# Shift_Register_Module_v0_6.net
KiCad netlist of a schematic drawn in EAGLE
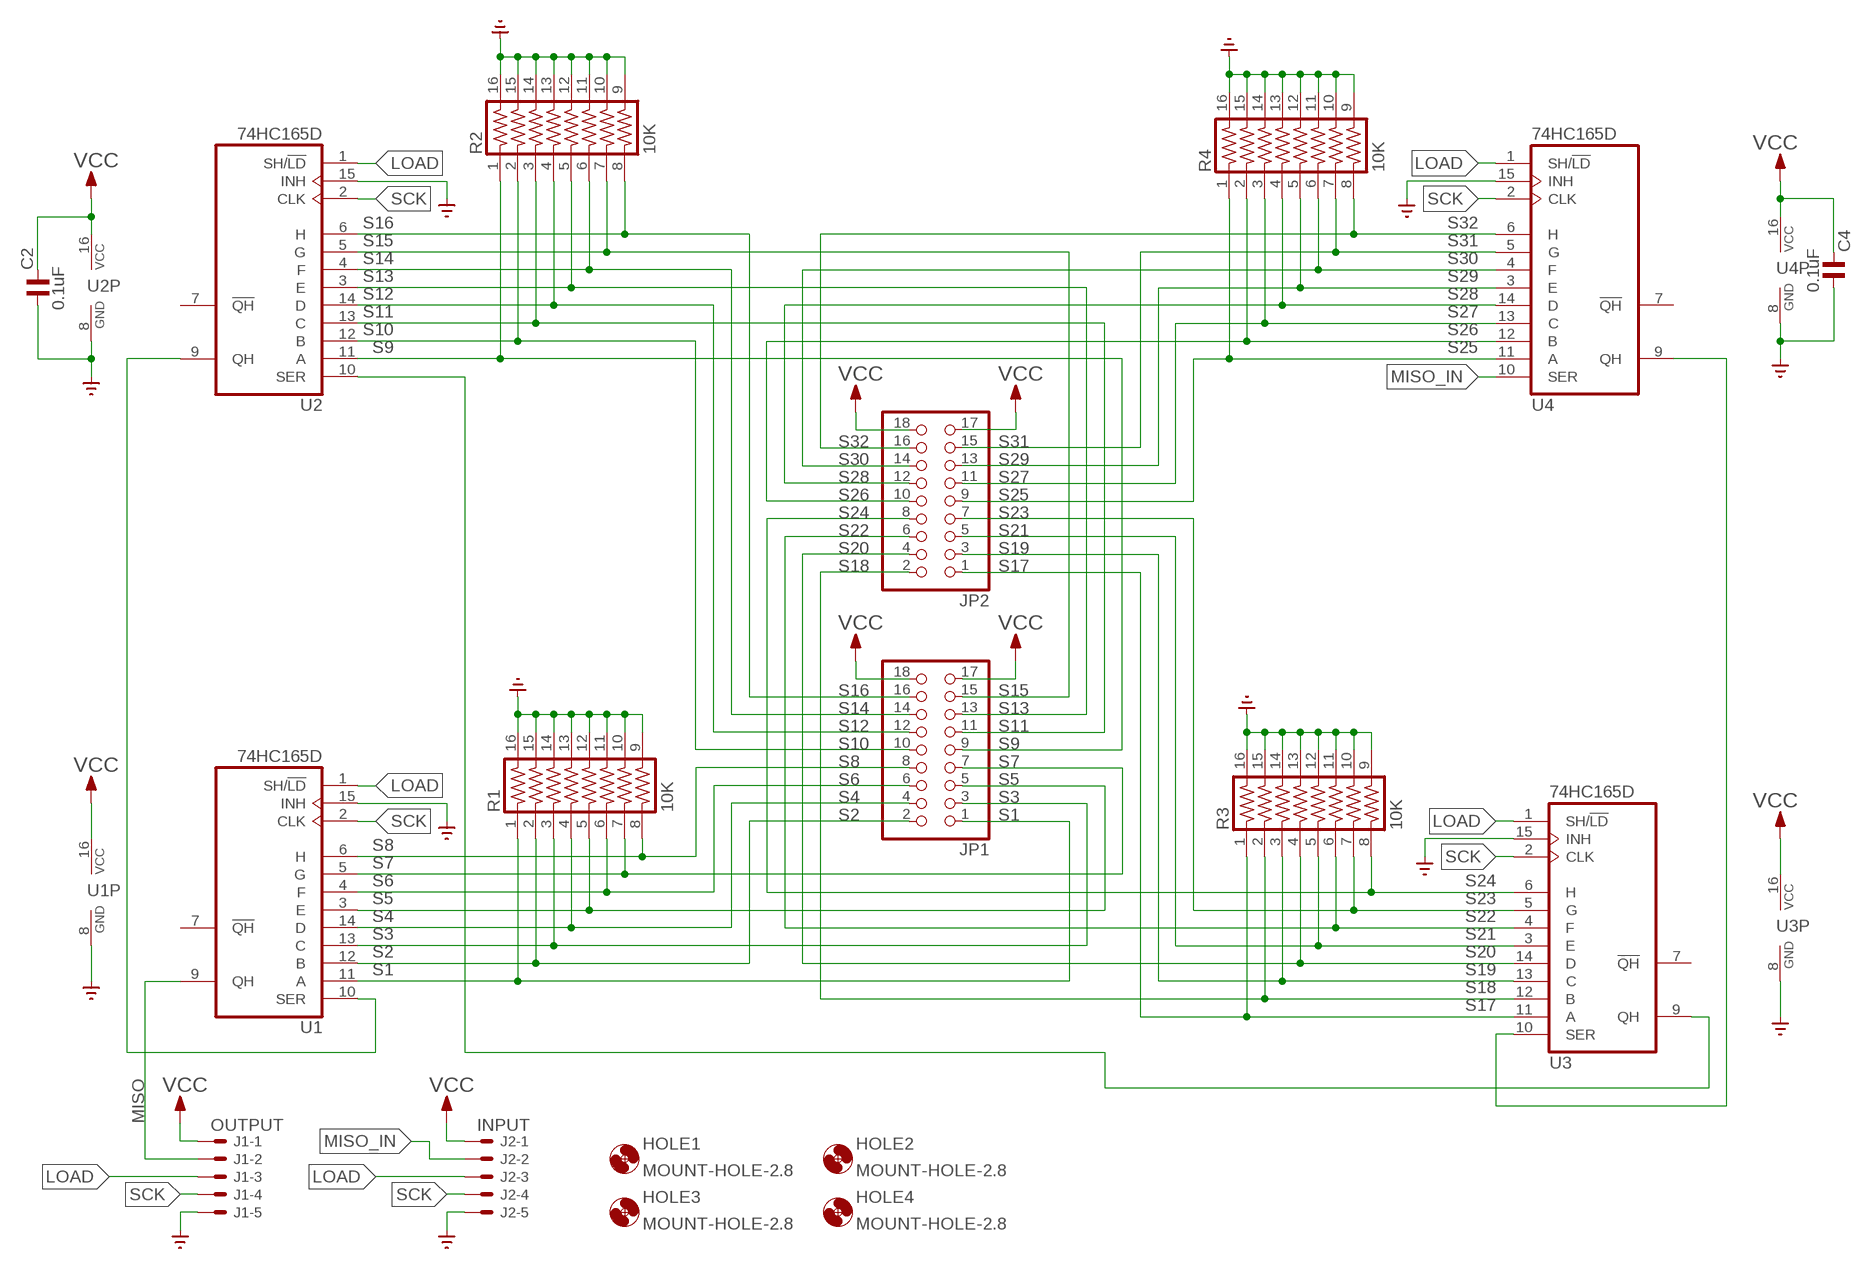
[diagram p0: schematic, sheet 1]

(export (version "E")
  (design (tool "Eeschema 10.0.6"))
  (components
    (comp (ref "C2")
      (value "0.1uF")
      (footprint "eagle-import:C0805MP")
      (libsource (lib "eagle-import") (part "C_0805MP"))
    )
    (comp (ref "C4")
      (value "0.1uF")
      (footprint "eagle-import:C0805MP")
      (libsource (lib "eagle-import") (part "C_0805MP"))
    )
    (comp (ref "HOLE1")
      (value "MOUNT-HOLE-2.8")
      (footprint "eagle-import:2,8")
      (libsource (lib "eagle-import") (part "MOUNT-HOLE-2.8"))
    )
    (comp (ref "HOLE2")
      (value "MOUNT-HOLE-2.8")
      (footprint "eagle-import:2,8")
      (libsource (lib "eagle-import") (part "MOUNT-HOLE-2.8"))
    )
    (comp (ref "HOLE3")
      (value "MOUNT-HOLE-2.8")
      (footprint "eagle-import:2,8")
      (libsource (lib "eagle-import") (part "MOUNT-HOLE-2.8"))
    )
    (comp (ref "HOLE4")
      (value "MOUNT-HOLE-2.8")
      (footprint "eagle-import:2,8")
      (libsource (lib "eagle-import") (part "MOUNT-HOLE-2.8"))
    )
    (comp (ref "J1")
      (value "OUTPUT")
      (footprint "eagle-import:7395-05")
      (libsource (lib "eagle-import") (part "22-?-0505-7058"))
    )
    (comp (ref "J2")
      (value "INPUT")
      (footprint "eagle-import:7395-05")
      (libsource (lib "eagle-import") (part "22-?-0505-7058"))
    )
    (comp (ref "JP1")
      (value "PINHD-2X9-SHROUDED")
      (footprint "eagle-import:2X09")
      (libsource (lib "eagle-import") (part "PINHD-2X9-SHROUDED"))
    )
    (comp (ref "JP2")
      (value "PINHD-2X9-SHROUDED")
      (footprint "eagle-import:2X09")
      (libsource (lib "eagle-import") (part "PINHD-2X9-SHROUDED"))
    )
    (comp (ref "R1")
      (value "10K")
      (footprint "eagle-import:4816P")
      (libsource (lib "eagle-import") (part "4816P-T01"))
    )
    (comp (ref "R2")
      (value "10K")
      (footprint "eagle-import:4816P")
      (libsource (lib "eagle-import") (part "4816P-T01"))
    )
    (comp (ref "R3")
      (value "10K")
      (footprint "eagle-import:4816P")
      (libsource (lib "eagle-import") (part "4816P-T01"))
    )
    (comp (ref "R4")
      (value "10K")
      (footprint "eagle-import:4816P")
      (libsource (lib "eagle-import") (part "4816P-T01"))
    )
    (comp (ref "U1")
      (value "74HC165D")
      (footprint "eagle-import:SO16")
      (libsource (lib "eagle-import") (part "74165DHC"))
    )
    (comp (ref "U2")
      (value "74HC165D")
      (footprint "eagle-import:SO16")
      (libsource (lib "eagle-import") (part "74165DHC"))
    )
    (comp (ref "U3")
      (value "74HC165D")
      (footprint "eagle-import:SO16")
      (libsource (lib "eagle-import") (part "74165DHC"))
    )
    (comp (ref "U4")
      (value "74HC165D")
      (footprint "eagle-import:SO16")
      (libsource (lib "eagle-import") (part "74165DHC"))
    )
  )
  (nets
    (net (code "1") (name "/MISO") (class "Default")
      (node (ref "J1") (pin "2") (pinfunction "S_2") (pintype "passive"))
      (node (ref "U1") (pin "9") (pinfunction "QH_9") (pintype "output"))
    )
    (net (code "2") (name "/S1") (class "Default")
      (node (ref "JP1") (pin "1") (pinfunction "1_1") (pintype "passive"))
      (node (ref "R1") (pin "1") (pinfunction "1_1") (pintype "passive"))
      (node (ref "U1") (pin "11") (pinfunction "A_11") (pintype "input"))
    )
    (net (code "3") (name "/S2") (class "Default")
      (node (ref "JP1") (pin "2") (pinfunction "2_2") (pintype "passive"))
      (node (ref "R1") (pin "2") (pinfunction "2_2") (pintype "passive"))
      (node (ref "U1") (pin "12") (pinfunction "B_12") (pintype "input"))
    )
    (net (code "4") (name "/S3") (class "Default")
      (node (ref "JP1") (pin "3") (pinfunction "3_3") (pintype "passive"))
      (node (ref "R1") (pin "3") (pinfunction "3_3") (pintype "passive"))
      (node (ref "U1") (pin "13") (pinfunction "C_13") (pintype "input"))
    )
    (net (code "5") (name "/S4") (class "Default")
      (node (ref "JP1") (pin "4") (pinfunction "4_4") (pintype "passive"))
      (node (ref "R1") (pin "4") (pinfunction "4_4") (pintype "passive"))
      (node (ref "U1") (pin "14") (pinfunction "D_14") (pintype "input"))
    )
    (net (code "6") (name "/S5") (class "Default")
      (node (ref "JP1") (pin "5") (pinfunction "5_5") (pintype "passive"))
      (node (ref "R1") (pin "5") (pinfunction "5_5") (pintype "passive"))
      (node (ref "U1") (pin "3") (pinfunction "E_3") (pintype "input"))
    )
    (net (code "7") (name "/S6") (class "Default")
      (node (ref "JP1") (pin "6") (pinfunction "6_6") (pintype "passive"))
      (node (ref "R1") (pin "6") (pinfunction "6_6") (pintype "passive"))
      (node (ref "U1") (pin "4") (pinfunction "F_4") (pintype "input"))
    )
    (net (code "8") (name "/S7") (class "Default")
      (node (ref "JP1") (pin "7") (pinfunction "7_7") (pintype "passive"))
      (node (ref "R1") (pin "7") (pinfunction "7_7") (pintype "passive"))
      (node (ref "U1") (pin "5") (pinfunction "G_5") (pintype "input"))
    )
    (net (code "9") (name "/S8") (class "Default")
      (node (ref "JP1") (pin "8") (pinfunction "8_8") (pintype "passive"))
      (node (ref "R1") (pin "8") (pinfunction "8_8") (pintype "passive"))
      (node (ref "U1") (pin "6") (pinfunction "H_6") (pintype "input"))
    )
    (net (code "10") (name "/S9") (class "Default")
      (node (ref "JP1") (pin "9") (pinfunction "9_9") (pintype "passive"))
      (node (ref "R2") (pin "1") (pinfunction "1_1") (pintype "passive"))
      (node (ref "U2") (pin "11") (pinfunction "A_11") (pintype "input"))
    )
    (net (code "11") (name "/S10") (class "Default")
      (node (ref "JP1") (pin "10") (pinfunction "10_10") (pintype "passive"))
      (node (ref "R2") (pin "2") (pinfunction "2_2") (pintype "passive"))
      (node (ref "U2") (pin "12") (pinfunction "B_12") (pintype "input"))
    )
    (net (code "12") (name "/S11") (class "Default")
      (node (ref "JP1") (pin "11") (pinfunction "11_11") (pintype "passive"))
      (node (ref "R2") (pin "3") (pinfunction "3_3") (pintype "passive"))
      (node (ref "U2") (pin "13") (pinfunction "C_13") (pintype "input"))
    )
    (net (code "13") (name "/S12") (class "Default")
      (node (ref "JP1") (pin "12") (pinfunction "12_12") (pintype "passive"))
      (node (ref "R2") (pin "4") (pinfunction "4_4") (pintype "passive"))
      (node (ref "U2") (pin "14") (pinfunction "D_14") (pintype "input"))
    )
    (net (code "14") (name "/S13") (class "Default")
      (node (ref "JP1") (pin "13") (pinfunction "13_13") (pintype "passive"))
      (node (ref "R2") (pin "5") (pinfunction "5_5") (pintype "passive"))
      (node (ref "U2") (pin "3") (pinfunction "E_3") (pintype "input"))
    )
    (net (code "15") (name "/S14") (class "Default")
      (node (ref "JP1") (pin "14") (pinfunction "14_14") (pintype "passive"))
      (node (ref "R2") (pin "6") (pinfunction "6_6") (pintype "passive"))
      (node (ref "U2") (pin "4") (pinfunction "F_4") (pintype "input"))
    )
    (net (code "16") (name "/S15") (class "Default")
      (node (ref "JP1") (pin "15") (pinfunction "15_15") (pintype "passive"))
      (node (ref "R2") (pin "7") (pinfunction "7_7") (pintype "passive"))
      (node (ref "U2") (pin "5") (pinfunction "G_5") (pintype "input"))
    )
    (net (code "17") (name "/S16") (class "Default")
      (node (ref "JP1") (pin "16") (pinfunction "16_16") (pintype "passive"))
      (node (ref "R2") (pin "8") (pinfunction "8_8") (pintype "passive"))
      (node (ref "U2") (pin "6") (pinfunction "H_6") (pintype "input"))
    )
    (net (code "18") (name "/S17") (class "Default")
      (node (ref "JP2") (pin "1") (pinfunction "1_1") (pintype "passive"))
      (node (ref "R3") (pin "1") (pinfunction "1_1") (pintype "passive"))
      (node (ref "U3") (pin "11") (pinfunction "A_11") (pintype "input"))
    )
    (net (code "19") (name "/S18") (class "Default")
      (node (ref "JP2") (pin "2") (pinfunction "2_2") (pintype "passive"))
      (node (ref "R3") (pin "2") (pinfunction "2_2") (pintype "passive"))
      (node (ref "U3") (pin "12") (pinfunction "B_12") (pintype "input"))
    )
    (net (code "20") (name "/S19") (class "Default")
      (node (ref "JP2") (pin "3") (pinfunction "3_3") (pintype "passive"))
      (node (ref "R3") (pin "3") (pinfunction "3_3") (pintype "passive"))
      (node (ref "U3") (pin "13") (pinfunction "C_13") (pintype "input"))
    )
    (net (code "21") (name "/S20") (class "Default")
      (node (ref "JP2") (pin "4") (pinfunction "4_4") (pintype "passive"))
      (node (ref "R3") (pin "4") (pinfunction "4_4") (pintype "passive"))
      (node (ref "U3") (pin "14") (pinfunction "D_14") (pintype "input"))
    )
    (net (code "22") (name "/S21") (class "Default")
      (node (ref "JP2") (pin "5") (pinfunction "5_5") (pintype "passive"))
      (node (ref "R3") (pin "5") (pinfunction "5_5") (pintype "passive"))
      (node (ref "U3") (pin "3") (pinfunction "E_3") (pintype "input"))
    )
    (net (code "23") (name "/S22") (class "Default")
      (node (ref "JP2") (pin "6") (pinfunction "6_6") (pintype "passive"))
      (node (ref "R3") (pin "6") (pinfunction "6_6") (pintype "passive"))
      (node (ref "U3") (pin "4") (pinfunction "F_4") (pintype "input"))
    )
    (net (code "24") (name "/S23") (class "Default")
      (node (ref "JP2") (pin "7") (pinfunction "7_7") (pintype "passive"))
      (node (ref "R3") (pin "7") (pinfunction "7_7") (pintype "passive"))
      (node (ref "U3") (pin "5") (pinfunction "G_5") (pintype "input"))
    )
    (net (code "25") (name "/S24") (class "Default")
      (node (ref "JP2") (pin "8") (pinfunction "8_8") (pintype "passive"))
      (node (ref "R3") (pin "8") (pinfunction "8_8") (pintype "passive"))
      (node (ref "U3") (pin "6") (pinfunction "H_6") (pintype "input"))
    )
    (net (code "26") (name "/S25") (class "Default")
      (node (ref "JP2") (pin "9") (pinfunction "9_9") (pintype "passive"))
      (node (ref "R4") (pin "1") (pinfunction "1_1") (pintype "passive"))
      (node (ref "U4") (pin "11") (pinfunction "A_11") (pintype "input"))
    )
    (net (code "27") (name "/S26") (class "Default")
      (node (ref "JP2") (pin "10") (pinfunction "10_10") (pintype "passive"))
      (node (ref "R4") (pin "2") (pinfunction "2_2") (pintype "passive"))
      (node (ref "U4") (pin "12") (pinfunction "B_12") (pintype "input"))
    )
    (net (code "28") (name "/S27") (class "Default")
      (node (ref "JP2") (pin "11") (pinfunction "11_11") (pintype "passive"))
      (node (ref "R4") (pin "3") (pinfunction "3_3") (pintype "passive"))
      (node (ref "U4") (pin "13") (pinfunction "C_13") (pintype "input"))
    )
    (net (code "29") (name "/S28") (class "Default")
      (node (ref "JP2") (pin "12") (pinfunction "12_12") (pintype "passive"))
      (node (ref "R4") (pin "4") (pinfunction "4_4") (pintype "passive"))
      (node (ref "U4") (pin "14") (pinfunction "D_14") (pintype "input"))
    )
    (net (code "30") (name "/S29") (class "Default")
      (node (ref "JP2") (pin "13") (pinfunction "13_13") (pintype "passive"))
      (node (ref "R4") (pin "5") (pinfunction "5_5") (pintype "passive"))
      (node (ref "U4") (pin "3") (pinfunction "E_3") (pintype "input"))
    )
    (net (code "31") (name "/S30") (class "Default")
      (node (ref "JP2") (pin "14") (pinfunction "14_14") (pintype "passive"))
      (node (ref "R4") (pin "6") (pinfunction "6_6") (pintype "passive"))
      (node (ref "U4") (pin "4") (pinfunction "F_4") (pintype "input"))
    )
    (net (code "32") (name "/S31") (class "Default")
      (node (ref "JP2") (pin "15") (pinfunction "15_15") (pintype "passive"))
      (node (ref "R4") (pin "7") (pinfunction "7_7") (pintype "passive"))
      (node (ref "U4") (pin "5") (pinfunction "G_5") (pintype "input"))
    )
    (net (code "33") (name "/S32") (class "Default")
      (node (ref "JP2") (pin "16") (pinfunction "16_16") (pintype "passive"))
      (node (ref "R4") (pin "8") (pinfunction "8_8") (pintype "passive"))
      (node (ref "U4") (pin "6") (pinfunction "H_6") (pintype "input"))
    )
    (net (code "34") (name "GND") (class "Default")
      (node (ref "C2") (pin "1") (pinfunction "1_1") (pintype "passive"))
      (node (ref "C4") (pin "1") (pinfunction "1_1") (pintype "passive"))
      (node (ref "J1") (pin "5") (pinfunction "S_5") (pintype "passive"))
      (node (ref "J2") (pin "5") (pinfunction "S_5") (pintype "passive"))
      (node (ref "R1") (pin "10") (pinfunction "10_10") (pintype "passive"))
      (node (ref "R1") (pin "11") (pinfunction "11_11") (pintype "passive"))
      (node (ref "R1") (pin "12") (pinfunction "12_12") (pintype "passive"))
      (node (ref "R1") (pin "13") (pinfunction "13_13") (pintype "passive"))
      (node (ref "R1") (pin "14") (pinfunction "14_14") (pintype "passive"))
      (node (ref "R1") (pin "15") (pinfunction "15_15") (pintype "passive"))
      (node (ref "R1") (pin "16") (pinfunction "16_16") (pintype "passive"))
      (node (ref "R1") (pin "9") (pinfunction "9_9") (pintype "passive"))
      (node (ref "R2") (pin "10") (pinfunction "10_10") (pintype "passive"))
      (node (ref "R2") (pin "11") (pinfunction "11_11") (pintype "passive"))
      (node (ref "R2") (pin "12") (pinfunction "12_12") (pintype "passive"))
      (node (ref "R2") (pin "13") (pinfunction "13_13") (pintype "passive"))
      (node (ref "R2") (pin "14") (pinfunction "14_14") (pintype "passive"))
      (node (ref "R2") (pin "15") (pinfunction "15_15") (pintype "passive"))
      (node (ref "R2") (pin "16") (pinfunction "16_16") (pintype "passive"))
      (node (ref "R2") (pin "9") (pinfunction "9_9") (pintype "passive"))
      (node (ref "R3") (pin "10") (pinfunction "10_10") (pintype "passive"))
      (node (ref "R3") (pin "11") (pinfunction "11_11") (pintype "passive"))
      (node (ref "R3") (pin "12") (pinfunction "12_12") (pintype "passive"))
      (node (ref "R3") (pin "13") (pinfunction "13_13") (pintype "passive"))
      (node (ref "R3") (pin "14") (pinfunction "14_14") (pintype "passive"))
      (node (ref "R3") (pin "15") (pinfunction "15_15") (pintype "passive"))
      (node (ref "R3") (pin "16") (pinfunction "16_16") (pintype "passive"))
      (node (ref "R3") (pin "9") (pinfunction "9_9") (pintype "passive"))
      (node (ref "R4") (pin "10") (pinfunction "10_10") (pintype "passive"))
      (node (ref "R4") (pin "11") (pinfunction "11_11") (pintype "passive"))
      (node (ref "R4") (pin "12") (pinfunction "12_12") (pintype "passive"))
      (node (ref "R4") (pin "13") (pinfunction "13_13") (pintype "passive"))
      (node (ref "R4") (pin "14") (pinfunction "14_14") (pintype "passive"))
      (node (ref "R4") (pin "15") (pinfunction "15_15") (pintype "passive"))
      (node (ref "R4") (pin "16") (pinfunction "16_16") (pintype "passive"))
      (node (ref "R4") (pin "9") (pinfunction "9_9") (pintype "passive"))
      (node (ref "U1") (pin "15") (pinfunction "INH_15") (pintype "input"))
      (node (ref "U1") (pin "8") (pinfunction "GND_8") (pintype "power_in"))
      (node (ref "U2") (pin "15") (pinfunction "INH_15") (pintype "input"))
      (node (ref "U2") (pin "8") (pinfunction "GND_8") (pintype "power_in"))
      (node (ref "U3") (pin "15") (pinfunction "INH_15") (pintype "input"))
      (node (ref "U3") (pin "8") (pinfunction "GND_8") (pintype "power_in"))
      (node (ref "U4") (pin "15") (pinfunction "INH_15") (pintype "input"))
      (node (ref "U4") (pin "8") (pinfunction "GND_8") (pintype "power_in"))
    )
    (net (code "35") (name "LOAD") (class "Default")
      (node (ref "J1") (pin "3") (pinfunction "S_3") (pintype "passive"))
      (node (ref "J2") (pin "3") (pinfunction "S_3") (pintype "passive"))
      (node (ref "U1") (pin "1") (pinfunction "SH/~{LD}_1") (pintype "input"))
      (node (ref "U2") (pin "1") (pinfunction "SH/~{LD}_1") (pintype "input"))
      (node (ref "U3") (pin "1") (pinfunction "SH/~{LD}_1") (pintype "input"))
      (node (ref "U4") (pin "1") (pinfunction "SH/~{LD}_1") (pintype "input"))
    )
    (net (code "36") (name "MISO_IN") (class "Default")
      (node (ref "J2") (pin "2") (pinfunction "S_2") (pintype "passive"))
      (node (ref "U4") (pin "10") (pinfunction "SER_10") (pintype "input"))
    )
    (net (code "37") (name "Net-(U1A-SER)") (class "Default")
      (node (ref "U1") (pin "10") (pinfunction "SER_10") (pintype "input"))
      (node (ref "U2") (pin "9") (pinfunction "QH_9") (pintype "output"))
    )
    (net (code "38") (name "Net-(U2A-SER)") (class "Default")
      (node (ref "U2") (pin "10") (pinfunction "SER_10") (pintype "input"))
      (node (ref "U3") (pin "9") (pinfunction "QH_9") (pintype "output"))
    )
    (net (code "39") (name "Net-(U3A-SER)") (class "Default")
      (node (ref "U3") (pin "10") (pinfunction "SER_10") (pintype "input"))
      (node (ref "U4") (pin "9") (pinfunction "QH_9") (pintype "output"))
    )
    (net (code "40") (name "SCK") (class "Default")
      (node (ref "J1") (pin "4") (pinfunction "S_4") (pintype "passive"))
      (node (ref "J2") (pin "4") (pinfunction "S_4") (pintype "passive"))
      (node (ref "U1") (pin "2") (pinfunction "CLK_2") (pintype "input"))
      (node (ref "U2") (pin "2") (pinfunction "CLK_2") (pintype "input"))
      (node (ref "U3") (pin "2") (pinfunction "CLK_2") (pintype "input"))
      (node (ref "U4") (pin "2") (pinfunction "CLK_2") (pintype "input"))
    )
    (net (code "41") (name "VCC") (class "Default")
      (node (ref "C2") (pin "2") (pinfunction "2_2") (pintype "passive"))
      (node (ref "C4") (pin "2") (pinfunction "2_2") (pintype "passive"))
      (node (ref "J1") (pin "1") (pinfunction "S_1") (pintype "passive"))
      (node (ref "J2") (pin "1") (pinfunction "S_1") (pintype "passive"))
      (node (ref "JP1") (pin "17") (pinfunction "17_17") (pintype "passive"))
      (node (ref "JP1") (pin "18") (pinfunction "18_18") (pintype "passive"))
      (node (ref "JP2") (pin "17") (pinfunction "17_17") (pintype "passive"))
      (node (ref "JP2") (pin "18") (pinfunction "18_18") (pintype "passive"))
      (node (ref "U1") (pin "16") (pinfunction "VCC_16") (pintype "power_in"))
      (node (ref "U2") (pin "16") (pinfunction "VCC_16") (pintype "power_in"))
      (node (ref "U3") (pin "16") (pinfunction "VCC_16") (pintype "power_in"))
      (node (ref "U4") (pin "16") (pinfunction "VCC_16") (pintype "power_in"))
    )
    (net (code "42") (name "unconnected-(U1A-~{QH}-Pad7)") (class "Default")
      (node (ref "U1") (pin "7") (pinfunction "~{QH}_7") (pintype "output"))
    )
    (net (code "43") (name "unconnected-(U2A-~{QH}-Pad7)") (class "Default")
      (node (ref "U2") (pin "7") (pinfunction "~{QH}_7") (pintype "output"))
    )
    (net (code "44") (name "unconnected-(U3A-~{QH}-Pad7)") (class "Default")
      (node (ref "U3") (pin "7") (pinfunction "~{QH}_7") (pintype "output"))
    )
    (net (code "45") (name "unconnected-(U4A-~{QH}-Pad7)") (class "Default")
      (node (ref "U4") (pin "7") (pinfunction "~{QH}_7") (pintype "output"))
    )
  )
)
